# amplifier.net
KiCad netlist of a schematic drawn in EAGLE
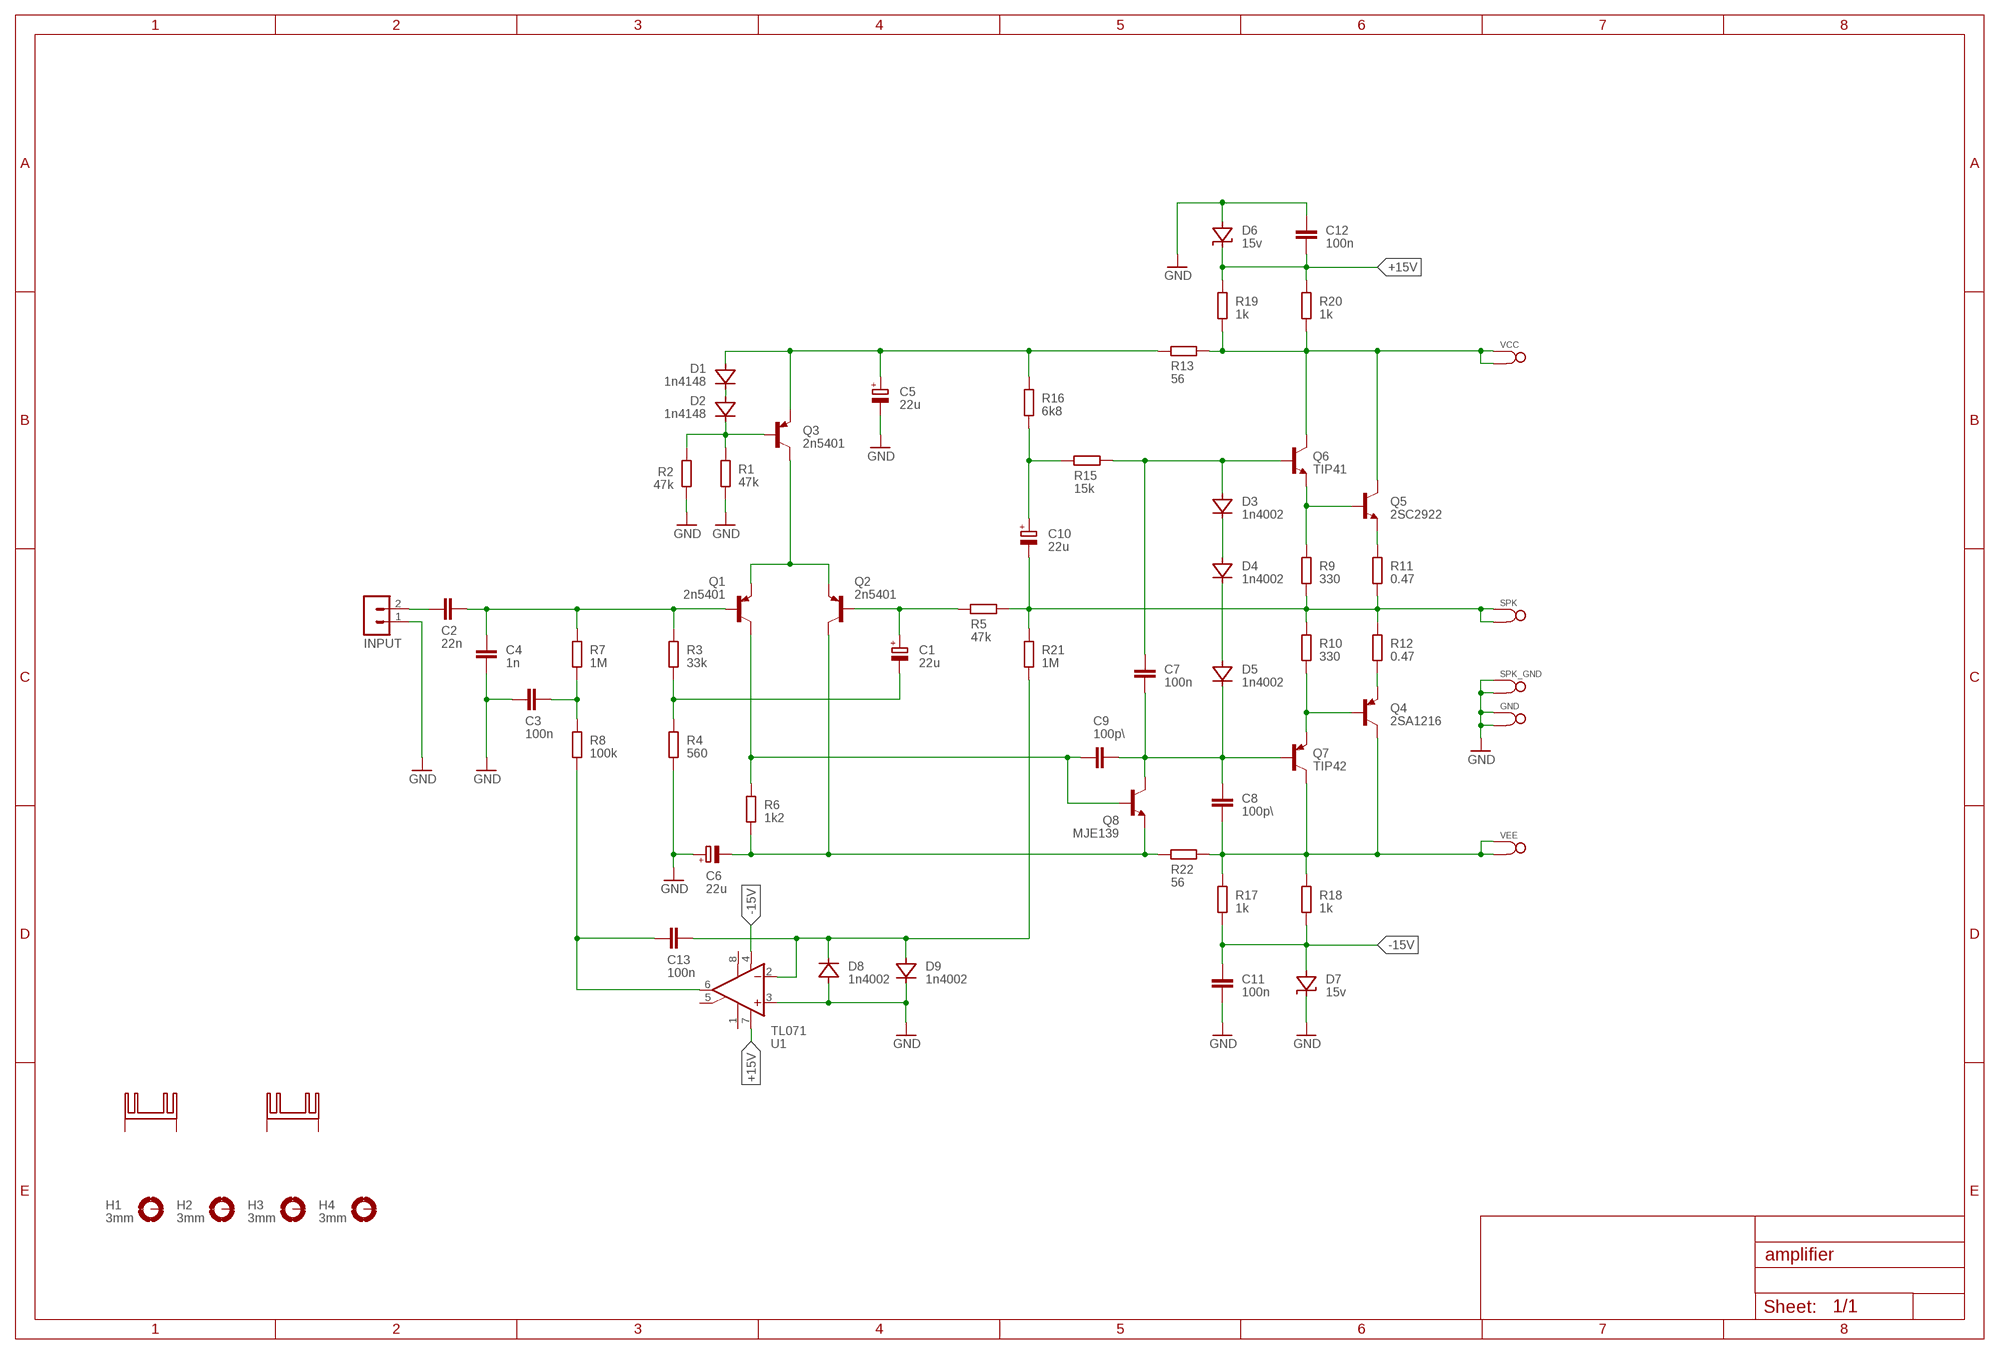
[diagram p0: schematic, sheet 1]

(export (version "E")
  (design (tool "Eeschema 10.0.6"))
  (components
    (comp (ref "C1")
      (value "22u")
      (footprint "eagle-import:E2,5-6")
      (libsource (lib "eagle-import") (part "C6"))
    )
    (comp (ref "C2")
      (value "22n")
      (footprint "eagle-import:C050-024X044")
      (libsource (lib "eagle-import") (part "C"))
    )
    (comp (ref "C3")
      (value "100n")
      (footprint "eagle-import:C050-024X044")
      (libsource (lib "eagle-import") (part "C"))
    )
    (comp (ref "C4")
      (value "1n")
      (footprint "eagle-import:C050-024X044")
      (libsource (lib "eagle-import") (part "C"))
    )
    (comp (ref "C5")
      (value "22u")
      (footprint "eagle-import:E3,5-8")
      (libsource (lib "eagle-import") (part "C8"))
    )
    (comp (ref "C6")
      (value "22u")
      (footprint "eagle-import:E3,5-8")
      (libsource (lib "eagle-import") (part "C8"))
    )
    (comp (ref "C7")
      (value "100n")
      (footprint "eagle-import:C050-024X044")
      (libsource (lib "eagle-import") (part "C"))
    )
    (comp (ref "C8")
      (value "100p\\")
      (footprint "eagle-import:C050-024X044")
      (libsource (lib "eagle-import") (part "C"))
    )
    (comp (ref "C9")
      (value "100p\\")
      (footprint "eagle-import:C050-024X044")
      (libsource (lib "eagle-import") (part "C"))
    )
    (comp (ref "C10")
      (value "22u")
      (footprint "eagle-import:E3,5-8")
      (libsource (lib "eagle-import") (part "C8"))
    )
    (comp (ref "C11")
      (value "100n")
      (footprint "eagle-import:C050-024X044")
      (libsource (lib "eagle-import") (part "C"))
    )
    (comp (ref "C12")
      (value "100n")
      (footprint "eagle-import:C050-024X044")
      (libsource (lib "eagle-import") (part "C"))
    )
    (comp (ref "C13")
      (value "100n")
      (footprint "eagle-import:C050-024X044")
      (libsource (lib "eagle-import") (part "C"))
    )
    (comp (ref "CON1")
      (value "INPUT")
      (footprint "eagle-import:2P")
      (libsource (lib "eagle-import") (part "JST-2P"))
    )
    (comp (ref "D1")
      (value "1n4148")
      (footprint "eagle-import:DO35Z7")
      (libsource (lib "eagle-import") (part "D"))
    )
    (comp (ref "D2")
      (value "1n4148")
      (footprint "eagle-import:DO35Z7")
      (libsource (lib "eagle-import") (part "D"))
    )
    (comp (ref "D3")
      (value "1n4002")
      (footprint "eagle-import:DO35Z7")
      (libsource (lib "eagle-import") (part "D"))
    )
    (comp (ref "D4")
      (value "1n4002")
      (footprint "eagle-import:DO35Z7")
      (libsource (lib "eagle-import") (part "D"))
    )
    (comp (ref "D5")
      (value "1n4002")
      (footprint "eagle-import:DO35Z7")
      (libsource (lib "eagle-import") (part "D"))
    )
    (comp (ref "D6")
      (value "15v")
      (footprint "eagle-import:DO35Z7")
      (libsource (lib "eagle-import") (part "DZ"))
    )
    (comp (ref "D7")
      (value "15v")
      (footprint "eagle-import:DO35Z7")
      (libsource (lib "eagle-import") (part "DZ"))
    )
    (comp (ref "D8")
      (value "1n4002")
      (footprint "eagle-import:DO35Z7")
      (libsource (lib "eagle-import") (part "D"))
    )
    (comp (ref "D9")
      (value "1n4002")
      (footprint "eagle-import:DO35Z7")
      (libsource (lib "eagle-import") (part "D"))
    )
    (comp (ref "GND")
      (value "SPADE")
      (footprint "eagle-import:SPADE-POWER")
      (libsource (lib "eagle-import") (part "SPADE"))
    )
    (comp (ref "H1")
      (value "3mm")
      (footprint "eagle-import:3,0-PAD")
      (libsource (lib "eagle-import") (part "MOUNT-PAD-ROUND3.0"))
    )
    (comp (ref "H2")
      (value "3mm")
      (footprint "eagle-import:3,0-PAD")
      (libsource (lib "eagle-import") (part "MOUNT-PAD-ROUND3.0"))
    )
    (comp (ref "H3")
      (value "3mm")
      (footprint "eagle-import:3,0-PAD")
      (libsource (lib "eagle-import") (part "MOUNT-PAD-ROUND3.0"))
    )
    (comp (ref "H4")
      (value "3mm")
      (footprint "eagle-import:3,0-PAD")
      (libsource (lib "eagle-import") (part "MOUNT-PAD-ROUND3.0"))
    )
    (comp (ref "KK1")
      (value "SK104-PAD")
      (footprint "eagle-import:SK104-PAD")
      (libsource (lib "eagle-import") (part "SK104-PAD"))
    )
    (comp (ref "KK2")
      (value "SK104-PAD")
      (footprint "eagle-import:SK104-PAD")
      (libsource (lib "eagle-import") (part "SK104-PAD"))
    )
    (comp (ref "Q1")
      (value "2n5401")
      (footprint "eagle-import:TO92-BCE")
      (libsource (lib "eagle-import") (part "PNP-TO92"))
    )
    (comp (ref "Q2")
      (value "2n5401")
      (footprint "eagle-import:TO92-BCE")
      (libsource (lib "eagle-import") (part "PNP-TO92"))
    )
    (comp (ref "Q3")
      (value "2n5401")
      (footprint "eagle-import:TO92-BCE")
      (libsource (lib "eagle-import") (part "PNP-TO92"))
    )
    (comp (ref "Q4")
      (value "2SA1216")
      (footprint "eagle-import:MT200L")
      (libsource (lib "eagle-import") (part "PNP-MT200"))
    )
    (comp (ref "Q5")
      (value "2SC2922")
      (footprint "eagle-import:MT200L")
      (libsource (lib "eagle-import") (part "NPN-MT200"))
    )
    (comp (ref "Q6")
      (value "TIP41")
      (footprint "eagle-import:TO220V")
      (libsource (lib "eagle-import") (part "NPN-TO220"))
    )
    (comp (ref "Q7")
      (value "TIP42")
      (footprint "eagle-import:TO220V")
      (libsource (lib "eagle-import") (part "PNP-TO220"))
    )
    (comp (ref "Q8")
      (value "MJE139")
      (footprint "eagle-import:TO126V")
      (libsource (lib "eagle-import") (part "NPN-TO126"))
    )
    (comp (ref "R1")
      (value "47k")
      (footprint "eagle-import:0309_12")
      (libsource (lib "eagle-import") (part "R0.5"))
    )
    (comp (ref "R2")
      (value "47k")
      (footprint "eagle-import:0309_12")
      (libsource (lib "eagle-import") (part "R0.5"))
    )
    (comp (ref "R3")
      (value "33k")
      (footprint "eagle-import:0309_12")
      (libsource (lib "eagle-import") (part "R0.5"))
    )
    (comp (ref "R4")
      (value "560")
      (footprint "eagle-import:0309_12")
      (libsource (lib "eagle-import") (part "R0.5"))
    )
    (comp (ref "R5")
      (value "47k")
      (footprint "eagle-import:0309_12")
      (libsource (lib "eagle-import") (part "R0.5"))
    )
    (comp (ref "R6")
      (value "1k2")
      (footprint "eagle-import:0309_12")
      (libsource (lib "eagle-import") (part "R0.5"))
    )
    (comp (ref "R7")
      (value "1M")
      (footprint "eagle-import:0309_12")
      (libsource (lib "eagle-import") (part "R0.5"))
    )
    (comp (ref "R8")
      (value "100k")
      (footprint "eagle-import:0309_12")
      (libsource (lib "eagle-import") (part "R0.5"))
    )
    (comp (ref "R9")
      (value "330")
      (footprint "eagle-import:0617_17")
      (libsource (lib "eagle-import") (part "R2"))
    )
    (comp (ref "R10")
      (value "330")
      (footprint "eagle-import:0617_17")
      (libsource (lib "eagle-import") (part "R2"))
    )
    (comp (ref "R11")
      (value "0.47")
      (footprint "eagle-import:0922_22")
      (libsource (lib "eagle-import") (part "R5"))
    )
    (comp (ref "R12")
      (value "0.47")
      (footprint "eagle-import:0922_22")
      (libsource (lib "eagle-import") (part "R5"))
    )
    (comp (ref "R13")
      (value "56")
      (footprint "eagle-import:0309_12")
      (libsource (lib "eagle-import") (part "R0.5"))
    )
    (comp (ref "R15")
      (value "15k")
      (footprint "eagle-import:0309_12")
      (libsource (lib "eagle-import") (part "R0.5"))
    )
    (comp (ref "R16")
      (value "6k8")
      (footprint "eagle-import:0309_12")
      (libsource (lib "eagle-import") (part "R0.5"))
    )
    (comp (ref "R17")
      (value "1k")
      (footprint "eagle-import:0309_12")
      (libsource (lib "eagle-import") (part "R0.5"))
    )
    (comp (ref "R18")
      (value "1k")
      (footprint "eagle-import:0309_12")
      (libsource (lib "eagle-import") (part "R0.5"))
    )
    (comp (ref "R19")
      (value "1k")
      (footprint "eagle-import:0309_12")
      (libsource (lib "eagle-import") (part "R0.5"))
    )
    (comp (ref "R20")
      (value "1k")
      (footprint "eagle-import:0309_12")
      (libsource (lib "eagle-import") (part "R0.5"))
    )
    (comp (ref "R21")
      (value "1M")
      (footprint "eagle-import:0309_12")
      (libsource (lib "eagle-import") (part "R0.5"))
    )
    (comp (ref "R22")
      (value "56")
      (footprint "eagle-import:0309_12")
      (libsource (lib "eagle-import") (part "R0.5"))
    )
    (comp (ref "SPK")
      (value "SPADE")
      (footprint "eagle-import:SPADE-POWER")
      (libsource (lib "eagle-import") (part "SPADE"))
    )
    (comp (ref "SPK_GND")
      (value "SPADE")
      (footprint "eagle-import:SPADE-POWER")
      (libsource (lib "eagle-import") (part "SPADE"))
    )
    (comp (ref "U1")
      (value "TL071")
      (footprint "eagle-import:DIL08")
      (libsource (lib "eagle-import") (part "TL071"))
    )
    (comp (ref "VCC")
      (value "SPADE")
      (footprint "eagle-import:SPADE-POWER")
      (libsource (lib "eagle-import") (part "SPADE"))
    )
    (comp (ref "VEE")
      (value "SPADE")
      (footprint "eagle-import:SPADE-POWER")
      (libsource (lib "eagle-import") (part "SPADE"))
    )
  )
  (nets
    (net (code "1") (name "+15V") (class "Default")
      (node (ref "C12") (pin "1") (pinfunction "1_1") (pintype "passive"))
      (node (ref "D6") (pin "C") (pinfunction "C_C") (pintype "passive"))
      (node (ref "R19") (pin "2") (pinfunction "2_2") (pintype "passive"))
      (node (ref "R20") (pin "2") (pinfunction "2_2") (pintype "passive"))
      (node (ref "U1") (pin "7") (pinfunction "V+_7") (pintype "power_in"))
    )
    (net (code "2") (name "-15V") (class "Default")
      (node (ref "C11") (pin "2") (pinfunction "2_2") (pintype "passive"))
      (node (ref "D7") (pin "A") (pinfunction "A_A") (pintype "passive"))
      (node (ref "R17") (pin "1") (pinfunction "1_1") (pintype "passive"))
      (node (ref "R18") (pin "1") (pinfunction "1_1") (pintype "passive"))
      (node (ref "U1") (pin "4") (pinfunction "V-_4") (pintype "power_in"))
    )
    (net (code "3") (name "GND") (class "Default")
      (node (ref "C11") (pin "1") (pinfunction "1_1") (pintype "passive"))
      (node (ref "C12") (pin "2") (pinfunction "2_2") (pintype "passive"))
      (node (ref "C3") (pin "1") (pinfunction "1_1") (pintype "passive"))
      (node (ref "C4") (pin "1") (pinfunction "1_1") (pintype "passive"))
      (node (ref "C5") (pin "-") (pinfunction "-_-") (pintype "passive"))
      (node (ref "C6") (pin "+") (pinfunction "+_+") (pintype "passive"))
      (node (ref "CON1") (pin "1") (pinfunction "1_1") (pintype "passive"))
      (node (ref "D6") (pin "A") (pinfunction "A_A") (pintype "passive"))
      (node (ref "D7") (pin "C") (pinfunction "C_C") (pintype "passive"))
      (node (ref "D8") (pin "A") (pinfunction "A_A") (pintype "passive"))
      (node (ref "D9") (pin "C") (pinfunction "C_C") (pintype "passive"))
      (node (ref "GND") (pin "P$1") (pinfunction "P$1_P$1") (pintype "bidirectional"))
      (node (ref "GND") (pin "P$2") (pinfunction "P$2_P$2") (pintype "bidirectional"))
      (node (ref "R1") (pin "1") (pinfunction "1_1") (pintype "passive"))
      (node (ref "R2") (pin "1") (pinfunction "1_1") (pintype "passive"))
      (node (ref "R4") (pin "1") (pinfunction "1_1") (pintype "passive"))
      (node (ref "SPK_GND") (pin "P$1") (pinfunction "P$1_P$1") (pintype "bidirectional"))
      (node (ref "SPK_GND") (pin "P$2") (pinfunction "P$2_P$2") (pintype "bidirectional"))
      (node (ref "U1") (pin "3") (pinfunction "+IN_3") (pintype "input"))
    )
    (net (code "4") (name "Net-(C1-Pad+)") (class "Default")
      (node (ref "C1") (pin "+") (pinfunction "+_+") (pintype "passive"))
      (node (ref "Q2") (pin "B") (pinfunction "B_B") (pintype "passive"))
      (node (ref "R5") (pin "2") (pinfunction "2_2") (pintype "passive"))
    )
    (net (code "5") (name "Net-(C1-Pad-)") (class "Default")
      (node (ref "C1") (pin "-") (pinfunction "-_-") (pintype "passive"))
      (node (ref "R3") (pin "1") (pinfunction "1_1") (pintype "passive"))
      (node (ref "R4") (pin "2") (pinfunction "2_2") (pintype "passive"))
    )
    (net (code "6") (name "Net-(C2-Pad1)") (class "Default")
      (node (ref "C2") (pin "1") (pinfunction "1_1") (pintype "passive"))
      (node (ref "CON1") (pin "2") (pinfunction "2_2") (pintype "passive"))
    )
    (net (code "7") (name "Net-(C2-Pad2)") (class "Default")
      (node (ref "C2") (pin "2") (pinfunction "2_2") (pintype "passive"))
      (node (ref "C4") (pin "2") (pinfunction "2_2") (pintype "passive"))
      (node (ref "Q1") (pin "B") (pinfunction "B_B") (pintype "passive"))
      (node (ref "R3") (pin "2") (pinfunction "2_2") (pintype "passive"))
      (node (ref "R7") (pin "2") (pinfunction "2_2") (pintype "passive"))
    )
    (net (code "8") (name "Net-(C3-Pad2)") (class "Default")
      (node (ref "C3") (pin "2") (pinfunction "2_2") (pintype "passive"))
      (node (ref "R7") (pin "1") (pinfunction "1_1") (pintype "passive"))
      (node (ref "R8") (pin "2") (pinfunction "2_2") (pintype "passive"))
    )
    (net (code "9") (name "Net-(C5-Pad+)") (class "Default")
      (node (ref "C5") (pin "+") (pinfunction "+_+") (pintype "passive"))
      (node (ref "D1") (pin "A") (pinfunction "A_A") (pintype "passive"))
      (node (ref "Q3") (pin "E") (pinfunction "E_E") (pintype "passive"))
      (node (ref "R13") (pin "2") (pinfunction "2_2") (pintype "passive"))
      (node (ref "R16") (pin "2") (pinfunction "2_2") (pintype "passive"))
    )
    (net (code "10") (name "Net-(C6-Pad-)") (class "Default")
      (node (ref "C6") (pin "-") (pinfunction "-_-") (pintype "passive"))
      (node (ref "Q2") (pin "C") (pinfunction "C_C") (pintype "passive"))
      (node (ref "Q8") (pin "E") (pinfunction "E_E") (pintype "passive"))
      (node (ref "R22") (pin "2") (pinfunction "2_2") (pintype "passive"))
      (node (ref "R6") (pin "1") (pinfunction "1_1") (pintype "passive"))
    )
    (net (code "11") (name "Net-(C7-Pad1)") (class "Default")
      (node (ref "C7") (pin "1") (pinfunction "1_1") (pintype "passive"))
      (node (ref "C8") (pin "1") (pinfunction "1_1") (pintype "passive"))
      (node (ref "C9") (pin "2") (pinfunction "2_2") (pintype "passive"))
      (node (ref "D5") (pin "C") (pinfunction "C_C") (pintype "passive"))
      (node (ref "Q7") (pin "B") (pinfunction "B_B") (pintype "passive"))
      (node (ref "Q8") (pin "C") (pinfunction "C_C") (pintype "passive"))
    )
    (net (code "12") (name "Net-(C7-Pad2)") (class "Default")
      (node (ref "C7") (pin "2") (pinfunction "2_2") (pintype "passive"))
      (node (ref "D3") (pin "A") (pinfunction "A_A") (pintype "passive"))
      (node (ref "Q6") (pin "B") (pinfunction "B_B") (pintype "passive"))
      (node (ref "R15") (pin "1") (pinfunction "1_1") (pintype "passive"))
    )
    (net (code "13") (name "Net-(C8-Pad2)") (class "Default")
      (node (ref "C8") (pin "2") (pinfunction "2_2") (pintype "passive"))
      (node (ref "Q4") (pin "C") (pinfunction "C_C") (pintype "passive"))
      (node (ref "Q7") (pin "C") (pinfunction "C_C") (pintype "passive"))
      (node (ref "R17") (pin "2") (pinfunction "2_2") (pintype "passive"))
      (node (ref "R18") (pin "2") (pinfunction "2_2") (pintype "passive"))
      (node (ref "R22") (pin "1") (pinfunction "1_1") (pintype "passive"))
      (node (ref "VEE") (pin "P$1") (pinfunction "P$1_P$1") (pintype "bidirectional"))
      (node (ref "VEE") (pin "P$2") (pinfunction "P$2_P$2") (pintype "bidirectional"))
    )
    (net (code "14") (name "Net-(C9-Pad1)") (class "Default")
      (node (ref "C9") (pin "1") (pinfunction "1_1") (pintype "passive"))
      (node (ref "Q1") (pin "C") (pinfunction "C_C") (pintype "passive"))
      (node (ref "Q8") (pin "B") (pinfunction "B_B") (pintype "passive"))
      (node (ref "R6") (pin "2") (pinfunction "2_2") (pintype "passive"))
    )
    (net (code "15") (name "Net-(C10-Pad+)") (class "Default")
      (node (ref "C10") (pin "+") (pinfunction "+_+") (pintype "passive"))
      (node (ref "R15") (pin "2") (pinfunction "2_2") (pintype "passive"))
      (node (ref "R16") (pin "1") (pinfunction "1_1") (pintype "passive"))
    )
    (net (code "16") (name "Net-(C10-Pad-)") (class "Default")
      (node (ref "C10") (pin "-") (pinfunction "-_-") (pintype "passive"))
      (node (ref "R10") (pin "2") (pinfunction "2_2") (pintype "passive"))
      (node (ref "R11") (pin "1") (pinfunction "1_1") (pintype "passive"))
      (node (ref "R12") (pin "2") (pinfunction "2_2") (pintype "passive"))
      (node (ref "R21") (pin "2") (pinfunction "2_2") (pintype "passive"))
      (node (ref "R5") (pin "1") (pinfunction "1_1") (pintype "passive"))
      (node (ref "R9") (pin "1") (pinfunction "1_1") (pintype "passive"))
      (node (ref "SPK") (pin "P$1") (pinfunction "P$1_P$1") (pintype "bidirectional"))
      (node (ref "SPK") (pin "P$2") (pinfunction "P$2_P$2") (pintype "bidirectional"))
    )
    (net (code "17") (name "Net-(D1-PadC)") (class "Default")
      (node (ref "D1") (pin "C") (pinfunction "C_C") (pintype "passive"))
      (node (ref "D2") (pin "A") (pinfunction "A_A") (pintype "passive"))
    )
    (net (code "18") (name "Net-(D2-PadC)") (class "Default")
      (node (ref "D2") (pin "C") (pinfunction "C_C") (pintype "passive"))
      (node (ref "Q3") (pin "B") (pinfunction "B_B") (pintype "passive"))
      (node (ref "R1") (pin "2") (pinfunction "2_2") (pintype "passive"))
      (node (ref "R2") (pin "2") (pinfunction "2_2") (pintype "passive"))
    )
    (net (code "19") (name "Net-(D3-PadC)") (class "Default")
      (node (ref "D3") (pin "C") (pinfunction "C_C") (pintype "passive"))
      (node (ref "D4") (pin "A") (pinfunction "A_A") (pintype "passive"))
    )
    (net (code "20") (name "Net-(D4-PadC)") (class "Default")
      (node (ref "D4") (pin "C") (pinfunction "C_C") (pintype "passive"))
      (node (ref "D5") (pin "A") (pinfunction "A_A") (pintype "passive"))
    )
    (net (code "21") (name "Net-(Q1-PadE)") (class "Default")
      (node (ref "Q1") (pin "E") (pinfunction "E_E") (pintype "passive"))
      (node (ref "Q2") (pin "E") (pinfunction "E_E") (pintype "passive"))
      (node (ref "Q3") (pin "C") (pinfunction "C_C") (pintype "passive"))
    )
    (net (code "22") (name "Net-(Q4-PadB)") (class "Default")
      (node (ref "Q4") (pin "B") (pinfunction "B_B") (pintype "passive"))
      (node (ref "Q7") (pin "E") (pinfunction "E_E") (pintype "passive"))
      (node (ref "R10") (pin "1") (pinfunction "1_1") (pintype "passive"))
    )
    (net (code "23") (name "Net-(Q4-PadE)") (class "Default")
      (node (ref "Q4") (pin "E") (pinfunction "E_E") (pintype "passive"))
      (node (ref "R12") (pin "1") (pinfunction "1_1") (pintype "passive"))
    )
    (net (code "24") (name "Net-(Q5-PadB)") (class "Default")
      (node (ref "Q5") (pin "B") (pinfunction "B_B") (pintype "passive"))
      (node (ref "Q6") (pin "E") (pinfunction "E_E") (pintype "passive"))
      (node (ref "R9") (pin "2") (pinfunction "2_2") (pintype "passive"))
    )
    (net (code "25") (name "Net-(Q5-PadC)") (class "Default")
      (node (ref "Q5") (pin "C") (pinfunction "C_C") (pintype "passive"))
      (node (ref "Q6") (pin "C") (pinfunction "C_C") (pintype "passive"))
      (node (ref "R13") (pin "1") (pinfunction "1_1") (pintype "passive"))
      (node (ref "R19") (pin "1") (pinfunction "1_1") (pintype "passive"))
      (node (ref "R20") (pin "1") (pinfunction "1_1") (pintype "passive"))
      (node (ref "VCC") (pin "P$1") (pinfunction "P$1_P$1") (pintype "bidirectional"))
      (node (ref "VCC") (pin "P$2") (pinfunction "P$2_P$2") (pintype "bidirectional"))
    )
    (net (code "26") (name "Net-(Q5-PadE)") (class "Default")
      (node (ref "Q5") (pin "E") (pinfunction "E_E") (pintype "passive"))
      (node (ref "R11") (pin "2") (pinfunction "2_2") (pintype "passive"))
    )
    (net (code "27") (name "Net-(U1--IN)") (class "Default")
      (node (ref "C13") (pin "2") (pinfunction "2_2") (pintype "passive"))
      (node (ref "D8") (pin "C") (pinfunction "C_C") (pintype "passive"))
      (node (ref "D9") (pin "A") (pinfunction "A_A") (pintype "passive"))
      (node (ref "R21") (pin "1") (pinfunction "1_1") (pintype "passive"))
      (node (ref "U1") (pin "2") (pinfunction "-IN_2") (pintype "input"))
    )
    (net (code "28") (name "Net-(U1-OUT)") (class "Default")
      (node (ref "C13") (pin "1") (pinfunction "1_1") (pintype "passive"))
      (node (ref "R8") (pin "1") (pinfunction "1_1") (pintype "passive"))
      (node (ref "U1") (pin "6") (pinfunction "OUT_6") (pintype "output"))
    )
    (net (code "29") (name "unconnected-(H1-MOUNT-PadB3,0)") (class "Default")
      (node (ref "H1") (pin "B3,0") (pinfunction "MOUNT_B3,0") (pintype "passive"))
    )
    (net (code "30") (name "unconnected-(H2-MOUNT-PadB3,0)") (class "Default")
      (node (ref "H2") (pin "B3,0") (pinfunction "MOUNT_B3,0") (pintype "passive"))
    )
    (net (code "31") (name "unconnected-(H3-MOUNT-PadB3,0)") (class "Default")
      (node (ref "H3") (pin "B3,0") (pinfunction "MOUNT_B3,0") (pintype "passive"))
    )
    (net (code "32") (name "unconnected-(H4-MOUNT-PadB3,0)") (class "Default")
      (node (ref "H4") (pin "B3,0") (pinfunction "MOUNT_B3,0") (pintype "passive"))
    )
    (net (code "33") (name "unconnected-(KK1-K-PadK1)") (class "Default")
      (node (ref "KK1") (pin "K1") (pinfunction "K_K1") (pintype "passive"))
    )
    (net (code "34") (name "unconnected-(KK1-K-PadK2)") (class "Default")
      (node (ref "KK1") (pin "K2") (pinfunction "K_K2") (pintype "passive"))
    )
    (net (code "35") (name "unconnected-(KK2-K-PadK1)") (class "Default")
      (node (ref "KK2") (pin "K1") (pinfunction "K_K1") (pintype "passive"))
    )
    (net (code "36") (name "unconnected-(KK2-K-PadK2)") (class "Default")
      (node (ref "KK2") (pin "K2") (pinfunction "K_K2") (pintype "passive"))
    )
    (net (code "37") (name "unconnected-(U1-ON1-Pad1)") (class "Default")
      (node (ref "U1") (pin "1") (pinfunction "ON1_1") (pintype "passive"))
    )
    (net (code "38") (name "unconnected-(U1-ON2-Pad5)") (class "Default")
      (node (ref "U1") (pin "5") (pinfunction "ON2_5") (pintype "passive"))
    )
    (net (code "39") (name "unconnected-(U1-OPT-Pad8)") (class "Default")
      (node (ref "U1") (pin "8") (pinfunction "OPT_8") (pintype "passive"))
    )
  )
)
